# MCU.net
KiCad netlist of a schematic drawn in Altium Designer
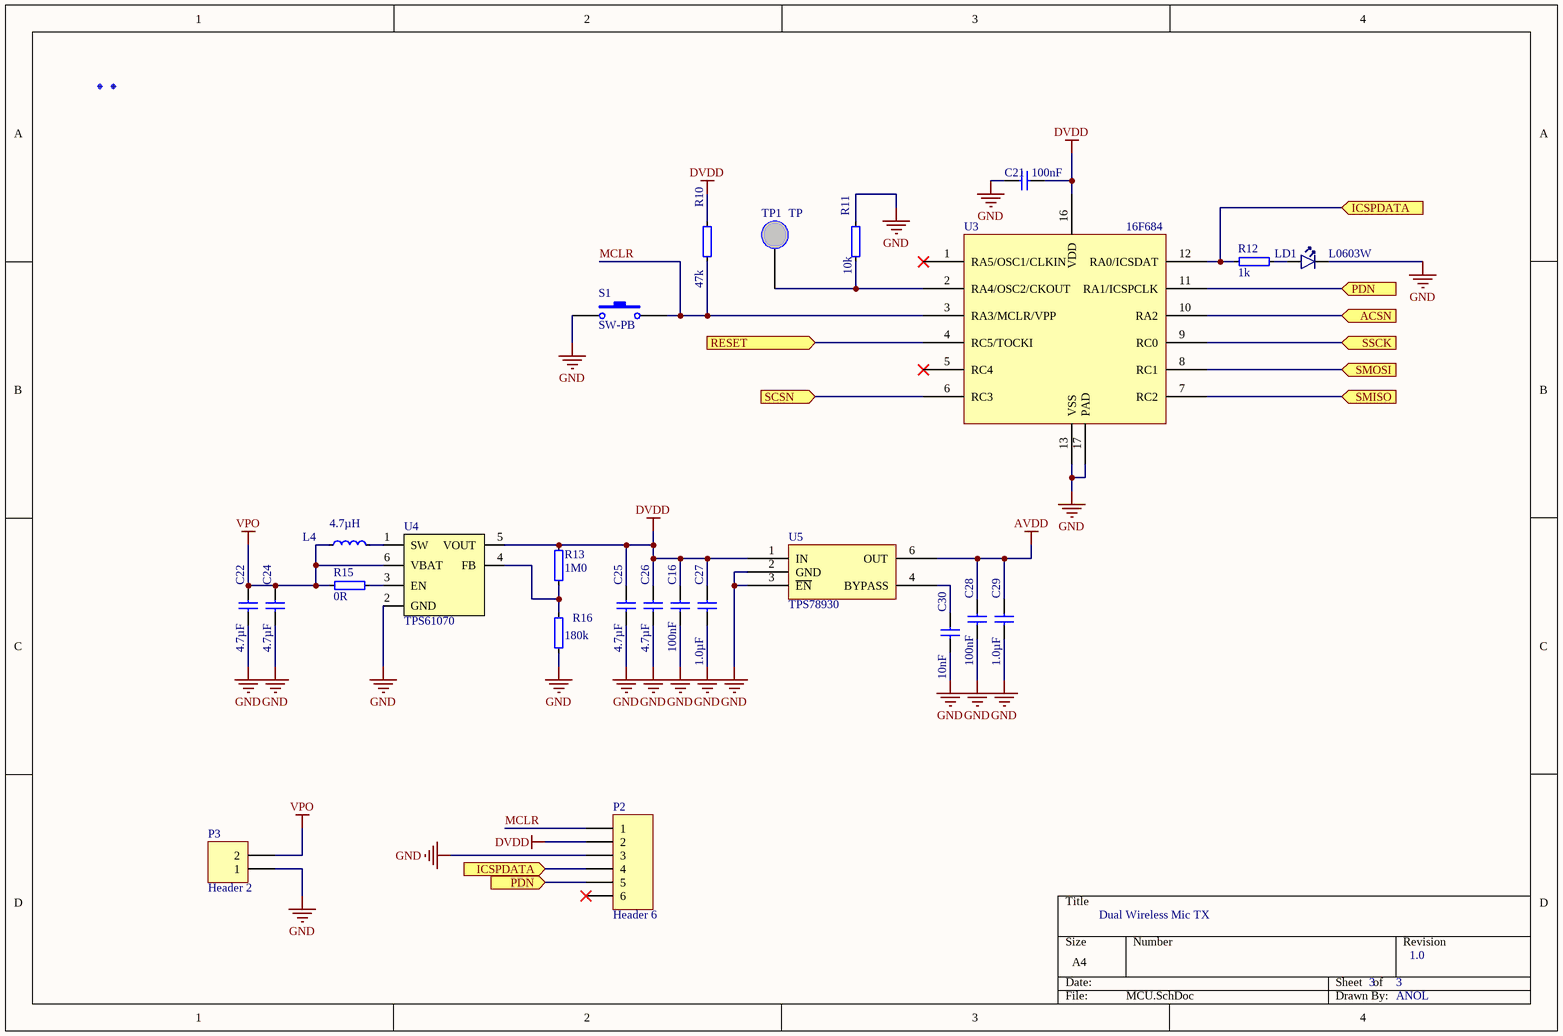
[diagram p0: MCU.SchDoc]

(export (version "E")
  (design (tool "Eeschema 10.0.6"))
  (components
    (comp (ref "C16")
      (value "100nF")
      (footprint "0402s")
      (description "Chip Cap 0402")
      (fields (field (name "PART NUMBER") "C0402-100n") (field (name "PUBLISHER") "Nordic Semiconductor"))
      (libsource (lib "Nordic Passive DB") (part "CAP"))
    )
    (comp (ref "C21")
      (value "100nF")
      (footprint "0402s")
      (description "Chip Cap 0402")
      (fields (field (name "PART NUMBER") "C0402-100n") (field (name "PUBLISHER") "Nordic Semiconductor"))
      (libsource (lib "Nordic Passive DB") (part "CAP"))
    )
    (comp (ref "C22")
      (value "4.7µF")
      (footprint "0603s")
      (description "Chip Cap 0603")
      (fields (field (name "PART NUMBER") "C0603-4µ7") (field (name "PUBLISHER") "Nordic Semiconductor"))
      (libsource (lib "Nordic Passive DB") (part "CAP"))
    )
    (comp (ref "C24")
      (value "4.7µF")
      (footprint "0603s")
      (description "Chip Cap 0603")
      (fields (field (name "PART NUMBER") "C0603-4µ7") (field (name "PUBLISHER") "Nordic Semiconductor"))
      (libsource (lib "Nordic Passive DB") (part "CAP"))
    )
    (comp (ref "C25")
      (value "4.7µF")
      (footprint "0603s")
      (description "Chip Cap 0603")
      (fields (field (name "PART NUMBER") "C0603-4µ7") (field (name "PUBLISHER") "Nordic Semiconductor"))
      (libsource (lib "Nordic Passive DB") (part "CAP"))
    )
    (comp (ref "C26")
      (value "4.7µF")
      (footprint "0603s")
      (description "Chip Cap 0603")
      (fields (field (name "PART NUMBER") "C0603-4µ7") (field (name "PUBLISHER") "Nordic Semiconductor"))
      (libsource (lib "Nordic Passive DB") (part "CAP"))
    )
    (comp (ref "C27")
      (value "1.0µF")
      (footprint "0603s")
      (description "Chip Cap 0603")
      (fields (field (name "PART NUMBER") "C0603-1µ0") (field (name "PUBLISHER") "Nordic Semiconductor"))
      (libsource (lib "Nordic Passive DB") (part "CAP"))
    )
    (comp (ref "C28")
      (value "100nF")
      (footprint "0402s")
      (description "Chip Cap 0402")
      (fields (field (name "PART NUMBER") "C0402-100n") (field (name "PUBLISHER") "Nordic Semiconductor"))
      (libsource (lib "Nordic Passive DB") (part "CAP"))
    )
    (comp (ref "C29")
      (value "1.0µF")
      (footprint "0603s")
      (description "Chip Cap 0603")
      (fields (field (name "PART NUMBER") "C0603-1µ0") (field (name "PUBLISHER") "Nordic Semiconductor"))
      (libsource (lib "Nordic Passive DB") (part "CAP"))
    )
    (comp (ref "C30")
      (value "10nF")
      (footprint "0402s")
      (description "Chip Cap 0402")
      (fields (field (name "PART NUMBER") "C0402-10n") (field (name "PUBLISHER") "Nordic Semiconductor"))
      (libsource (lib "Nordic Passive DB") (part "CAP"))
    )
    (comp (ref "Fid1")
      (value "Fiducial mark")
      (footprint "Fiducial")
      (description "Fiducial Mark")
      (fields (field (name "PART NUMBER") "Fid-Mark") (field (name "PUBLISHER") "Nordic Semiconductor"))
      (libsource (lib "Nordic Passive DB") (part "Fiducial"))
    )
    (comp (ref "Fid2")
      (value "Fiducial mark")
      (footprint "Fiducial")
      (description "Fiducial Mark")
      (fields (field (name "PART NUMBER") "Fid-Mark") (field (name "PUBLISHER") "Nordic Semiconductor"))
      (libsource (lib "Nordic Passive DB") (part "Fiducial"))
    )
    (comp (ref "L4")
      (value "4.7µH")
      (footprint "WE-TPC_TYPE_S")
      (description "Inductor Power 4.7uH 1.2A SMD")
      (fields
        (field (name "PART NUMBER") "WE-TPC Type S - 4µ7")
        (field (name "MANUFACTURER") "Wurth Elektronik")
        (field (name "PUBLISHER") "Nordic Semiconductor")
      )
      (libsource (lib "Nordic Passive DB") (part "IND"))
    )
    (comp (ref "LD1")
      (value "L0603W")
      (footprint "LED_0603")
      (description "LED 0603, 19-213/W1D")
      (fields
        (field (name "PART NUMBER") "19-213/W1D")
        (field (name "MANUFACTURER") "Everlight")
        (field (name "PUBLISHER") "Nordic Semiconductor")
      )
      (libsource (lib "Nordic Discrete DB") (part "D{colon}LED"))
    )
    (comp (ref "P2")
      (value "Header 6")
      (footprint "HDR1X6")
      (description "Header, 6-Pin")
      (fields (field (name "PUBLISHER") "Altium Limited"))
      (libsource (lib "Miscellaneous Connectors") (part "Header 6"))
    )
    (comp (ref "P3")
      (value "Header 2")
      (footprint "HDR1X2")
      (description "Header, 2-Pin")
      (fields (field (name "PUBLISHER") "Altium Limited"))
      (libsource (lib "Miscellaneous Connectors") (part "Header 2"))
    )
    (comp (ref "R10")
      (value "47k")
      (footprint "0402s")
      (description "Chip Res 0402")
      (fields (field (name "PART NUMBER") "R0402-47k") (field (name "PUBLISHER") "Nordic Semiconductor"))
      (libsource (lib "Nordic Passive DB") (part "RES_1"))
    )
    (comp (ref "R11")
      (value "10k")
      (footprint "0402s")
      (description "Chip Res 0402")
      (fields (field (name "PART NUMBER") "R0402-10k") (field (name "PUBLISHER") "Nordic Semiconductor"))
      (libsource (lib "Nordic Passive DB") (part "RES_1"))
    )
    (comp (ref "R12")
      (value "1k")
      (footprint "0402s")
      (description "Chip Res 0402")
      (fields (field (name "PART NUMBER") "R0402-1k0") (field (name "PUBLISHER") "Nordic Semiconductor"))
      (libsource (lib "Nordic Passive DB") (part "RES_1"))
    )
    (comp (ref "R13")
      (value "1M0")
      (footprint "0402s")
      (description "Chip Res 0402")
      (fields (field (name "PART NUMBER") "R0402-1M0") (field (name "PUBLISHER") "Nordic Semiconductor"))
      (libsource (lib "Nordic Passive DB") (part "RES_1"))
    )
    (comp (ref "R15")
      (value "0R")
      (footprint "0402s")
      (description "Chip Res 0402")
      (fields (field (name "PART NUMBER") "R0402-0R") (field (name "PUBLISHER") "Nordic Semiconductor"))
      (libsource (lib "Nordic Passive DB") (part "RES_1"))
    )
    (comp (ref "R16")
      (value "180k")
      (footprint "0402s")
      (description "Chip Res 0402")
      (fields (field (name "PART NUMBER") "R0402-180k") (field (name "PUBLISHER") "Nordic Semiconductor"))
      (libsource (lib "Nordic Passive DB") (part "RES_1"))
    )
    (comp (ref "S1")
      (value "SW-PB")
      (footprint "E-Switch")
      (description "Switch")
      (fields (field (name "PUBLISHER") "Altium Limited"))
      (libsource (lib "Miscellaneous Devices") (part "SW-PB"))
    )
    (comp (ref "TP1") (value "TP") (footprint "TP") (libsource (lib "nRF2460") (part "TP")))
    (comp (ref "U3")
      (value "16F684")
      (footprint "QFN65P400X400X100-16N")
      (libsource (lib "nRF2460") (part "16F684"))
    )
    (comp (ref "U4")
      (value "TPS61070")
      (footprint "SOT95P280X110-6N")
      (description "IC BOOST CONV 600MA SW TSOT23-6")
      (fields
        (field (name "MANUFACTURER") "Texas Instruments")
        (field (name "MANUFACTURER PART NUMBER") "TPS61070DDCR")
        (field (name "PUBLISHER") "Nordic Semiconductor")
      )
      (libsource (lib "Nordic Active DB") (part "TPS6107x"))
    )
    (comp (ref "U5")
      (value "TPS78930")
      (footprint "SOT95P280X145-6N")
      (libsource (lib "nRF2460") (part "TPS78930"))
    )
  )
  (nets
    (net (code "1") (name "/ACSN") (class "Default")
      (node (ref "U3") (pin "10") (pinfunction "RA2_10") (pintype "passive"))
    )
    (net (code "2") (name "/ICSPDATA") (class "Default")
      (node (ref "P2") (pin "4") (pinfunction "4_4") (pintype "passive"))
      (node (ref "R12") (pin "1") (pinfunction "1_1") (pintype "passive"))
      (node (ref "U3") (pin "12") (pinfunction "RA0/ICSDAT_12") (pintype "passive"))
    )
    (net (code "3") (name "/MCLR") (class "Default")
      (node (ref "P2") (pin "1") (pinfunction "1_1") (pintype "passive"))
      (node (ref "R10") (pin "1") (pinfunction "1_1") (pintype "passive"))
      (node (ref "S1") (pin "2") (pinfunction "2_2") (pintype "passive"))
      (node (ref "U3") (pin "3") (pinfunction "RA3/MCLR/VPP_3") (pintype "passive"))
    )
    (net (code "4") (name "/PDN") (class "Default")
      (node (ref "P2") (pin "5") (pinfunction "5_5") (pintype "passive"))
      (node (ref "U3") (pin "11") (pinfunction "RA1/ICSPCLK_11") (pintype "passive"))
    )
    (net (code "5") (name "/RESET") (class "Default")
      (node (ref "U3") (pin "4") (pinfunction "RC5/TOCKI_4") (pintype "passive"))
    )
    (net (code "6") (name "/SCSN") (class "Default")
      (node (ref "U3") (pin "6") (pinfunction "RC3_6") (pintype "passive"))
    )
    (net (code "7") (name "/SMISO") (class "Default")
      (node (ref "U3") (pin "7") (pinfunction "RC2_7") (pintype "passive"))
    )
    (net (code "8") (name "/SMOSI") (class "Default")
      (node (ref "U3") (pin "8") (pinfunction "RC1_8") (pintype "passive"))
    )
    (net (code "9") (name "/SSCK") (class "Default")
      (node (ref "U3") (pin "9") (pinfunction "RC0_9") (pintype "passive"))
    )
    (net (code "10") (name "AVDD") (class "Default")
      (node (ref "C28") (pin "2") (pinfunction "2_2") (pintype "passive"))
      (node (ref "C29") (pin "2") (pinfunction "2_2") (pintype "passive"))
      (node (ref "U5") (pin "6") (pinfunction "OUT_6") (pintype "power_in"))
    )
    (net (code "11") (name "DVDD") (class "Default")
      (node (ref "C16") (pin "2") (pinfunction "2_2") (pintype "passive"))
      (node (ref "C21") (pin "2") (pinfunction "2_2") (pintype "passive"))
      (node (ref "C25") (pin "2") (pinfunction "2_2") (pintype "passive"))
      (node (ref "C26") (pin "2") (pinfunction "2_2") (pintype "passive"))
      (node (ref "C27") (pin "2") (pinfunction "2_2") (pintype "passive"))
      (node (ref "P2") (pin "2") (pinfunction "2_2") (pintype "passive"))
      (node (ref "R10") (pin "2") (pinfunction "2_2") (pintype "passive"))
      (node (ref "R13") (pin "2") (pinfunction "2_2") (pintype "passive"))
      (node (ref "U3") (pin "16") (pinfunction "VDD_16") (pintype "passive"))
      (node (ref "U4") (pin "5") (pinfunction "VOUT_5") (pintype "passive"))
      (node (ref "U5") (pin "1") (pinfunction "IN_1") (pintype "passive"))
    )
    (net (code "12") (name "GND") (class "Default")
      (node (ref "C16") (pin "1") (pinfunction "1_1") (pintype "passive"))
      (node (ref "C21") (pin "1") (pinfunction "1_1") (pintype "passive"))
      (node (ref "C22") (pin "1") (pinfunction "1_1") (pintype "passive"))
      (node (ref "C24") (pin "1") (pinfunction "1_1") (pintype "passive"))
      (node (ref "C25") (pin "1") (pinfunction "1_1") (pintype "passive"))
      (node (ref "C26") (pin "1") (pinfunction "1_1") (pintype "passive"))
      (node (ref "C27") (pin "1") (pinfunction "1_1") (pintype "passive"))
      (node (ref "C28") (pin "1") (pinfunction "1_1") (pintype "passive"))
      (node (ref "C29") (pin "1") (pinfunction "1_1") (pintype "passive"))
      (node (ref "C30") (pin "1") (pinfunction "1_1") (pintype "passive"))
      (node (ref "LD1") (pin "1") (pinfunction "C_1") (pintype "passive"))
      (node (ref "P2") (pin "3") (pinfunction "3_3") (pintype "passive"))
      (node (ref "P3") (pin "1") (pinfunction "1_1") (pintype "passive"))
      (node (ref "R11") (pin "2") (pinfunction "2_2") (pintype "passive"))
      (node (ref "R16") (pin "1") (pinfunction "1_1") (pintype "passive"))
      (node (ref "S1") (pin "1") (pinfunction "1_1") (pintype "passive"))
      (node (ref "U3") (pin "13") (pinfunction "VSS_13") (pintype "passive"))
      (node (ref "U3") (pin "17") (pinfunction "PAD_17") (pintype "passive"))
      (node (ref "U4") (pin "2") (pinfunction "GND_2") (pintype "passive"))
      (node (ref "U5") (pin "2") (pinfunction "GND_2") (pintype "power_in"))
      (node (ref "U5") (pin "3") (pinfunction "~{EN}_3") (pintype "power_in"))
    )
    (net (code "13") (name "Net-(LD1-A)") (class "Default")
      (node (ref "LD1") (pin "2") (pinfunction "A_2") (pintype "passive"))
      (node (ref "R12") (pin "2") (pinfunction "2_2") (pintype "passive"))
    )
    (net (code "14") (name "Net-(U3-RA4{slash}OSC2{slash}CKOUT)") (class "Default")
      (node (ref "R11") (pin "1") (pinfunction "1_1") (pintype "passive"))
      (node (ref "TP1") (pin "1") (pintype "passive"))
      (node (ref "U3") (pin "2") (pinfunction "RA4/OSC2/CKOUT_2") (pintype "passive"))
    )
    (net (code "15") (name "Net-(U4-EN)") (class "Default")
      (node (ref "R15") (pin "2") (pinfunction "2_2") (pintype "passive"))
      (node (ref "U4") (pin "3") (pinfunction "EN_3") (pintype "passive"))
    )
    (net (code "16") (name "Net-(U4-FB)") (class "Default")
      (node (ref "R13") (pin "1") (pinfunction "1_1") (pintype "passive"))
      (node (ref "R16") (pin "2") (pinfunction "2_2") (pintype "passive"))
      (node (ref "U4") (pin "4") (pinfunction "FB_4") (pintype "passive"))
    )
    (net (code "17") (name "Net-(U4-SW)") (class "Default")
      (node (ref "L4") (pin "2") (pinfunction "2_2") (pintype "passive"))
      (node (ref "U4") (pin "1") (pinfunction "SW_1") (pintype "passive"))
    )
    (net (code "18") (name "Net-(U5-BYPASS)") (class "Default")
      (node (ref "C30") (pin "2") (pinfunction "2_2") (pintype "passive"))
      (node (ref "U5") (pin "4") (pinfunction "BYPASS_4") (pintype "power_in"))
    )
    (net (code "19") (name "VPO") (class "Default")
      (node (ref "C22") (pin "2") (pinfunction "2_2") (pintype "passive"))
      (node (ref "C24") (pin "2") (pinfunction "2_2") (pintype "passive"))
      (node (ref "L4") (pin "1") (pinfunction "1_1") (pintype "passive"))
      (node (ref "P3") (pin "2") (pinfunction "2_2") (pintype "passive"))
      (node (ref "R15") (pin "1") (pinfunction "1_1") (pintype "passive"))
      (node (ref "U4") (pin "6") (pinfunction "VBAT_6") (pintype "passive"))
    )
    (net (code "20") (name "unconnected-(P2-Pad6)") (class "Default")
      (node (ref "P2") (pin "6") (pinfunction "6_6") (pintype "passive+no_connect"))
    )
    (net (code "21") (name "unconnected-(U3-NC-Pad14)") (class "Default")
      (node (ref "U3") (pin "14") (pinfunction "NC_14") (pintype "passive"))
    )
    (net (code "22") (name "unconnected-(U3-NC-Pad15)") (class "Default")
      (node (ref "U3") (pin "15") (pinfunction "NC_15") (pintype "passive"))
    )
    (net (code "23") (name "unconnected-(U3-RA5{slash}OSC1{slash}CLKIN-Pad1)") (class "Default")
      (node (ref "U3") (pin "1") (pinfunction "RA5/OSC1/CLKIN_1") (pintype "passive+no_connect"))
    )
    (net (code "24") (name "unconnected-(U3-RC4-Pad5)") (class "Default")
      (node (ref "U3") (pin "5") (pinfunction "RC4_5") (pintype "passive+no_connect"))
    )
  )
)
